# TestResitorArraySmd.net
KiCad netlist of a schematic drawn in EAGLE
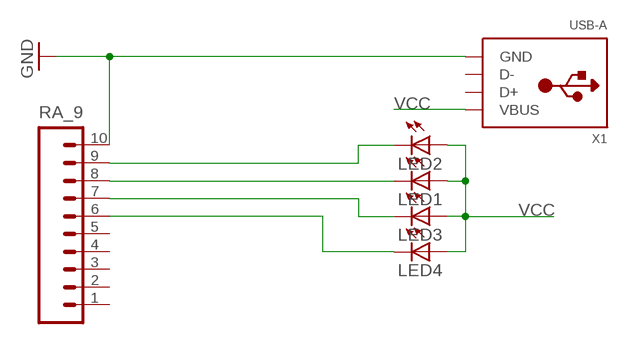
[diagram p0: schematic, sheet 1]

(export (version "E")
  (design (tool "Eeschema 10.0.6"))
  (components
    (comp (ref "LED1")
      (value "LEDSMT1206")
      (footprint "eagle-import:1206")
      (libsource (lib "eagle-import") (part "LEDSMT1206"))
    )
    (comp (ref "LED2")
      (value "LEDSMT1206")
      (footprint "eagle-import:1206")
      (libsource (lib "eagle-import") (part "LEDSMT1206"))
    )
    (comp (ref "LED3")
      (value "LEDSMT1206")
      (footprint "eagle-import:1206")
      (libsource (lib "eagle-import") (part "LEDSMT1206"))
    )
    (comp (ref "LED4")
      (value "LEDSMT1206")
      (footprint "eagle-import:1206")
      (libsource (lib "eagle-import") (part "LEDSMT1206"))
    )
    (comp (ref "RA_9")
      (value "M10SMD_MALE")
      (footprint "eagle-import:1X10_SMD_MALE")
      (libsource (lib "eagle-import") (part "M10SMD_MALE"))
    )
    (comp (ref "X1")
      (value "USB-A")
      (footprint "eagle-import:MOLEX_480371000")
      (libsource (lib "eagle-import") (part "USB-A"))
    )
  )
  (nets
    (net (code "1") (name "/VCC") (class "Default")
      (node (ref "LED1") (pin "A") (pinfunction "A_A") (pintype "passive"))
      (node (ref "LED2") (pin "A") (pinfunction "A_A") (pintype "passive"))
      (node (ref "LED3") (pin "A") (pinfunction "A_A") (pintype "passive"))
      (node (ref "LED4") (pin "A") (pinfunction "A_A") (pintype "passive"))
      (node (ref "X1") (pin "1") (pinfunction "VBUS_1") (pintype "power_in"))
    )
    (net (code "2") (name "GND") (class "Default")
      (node (ref "RA_9") (pin "10") (pinfunction "10_10") (pintype "passive"))
      (node (ref "X1") (pin "4") (pinfunction "GND_4") (pintype "power_in"))
    )
    (net (code "3") (name "Net-(LED1-PadC)") (class "Default")
      (node (ref "LED1") (pin "C") (pinfunction "C_C") (pintype "passive"))
      (node (ref "RA_9") (pin "8") (pinfunction "8_8") (pintype "passive"))
    )
    (net (code "4") (name "Net-(LED2-PadC)") (class "Default")
      (node (ref "LED2") (pin "C") (pinfunction "C_C") (pintype "passive"))
      (node (ref "RA_9") (pin "9") (pinfunction "9_9") (pintype "passive"))
    )
    (net (code "5") (name "Net-(LED3-PadC)") (class "Default")
      (node (ref "LED3") (pin "C") (pinfunction "C_C") (pintype "passive"))
      (node (ref "RA_9") (pin "7") (pinfunction "7_7") (pintype "passive"))
    )
    (net (code "6") (name "Net-(LED4-PadC)") (class "Default")
      (node (ref "LED4") (pin "C") (pinfunction "C_C") (pintype "passive"))
      (node (ref "RA_9") (pin "6") (pinfunction "6_6") (pintype "passive"))
    )
    (net (code "7") (name "unconnected-(RA_9-Pad1)") (class "Default")
      (node (ref "RA_9") (pin "1") (pinfunction "1_1") (pintype "passive"))
    )
    (net (code "8") (name "unconnected-(RA_9-Pad2)") (class "Default")
      (node (ref "RA_9") (pin "2") (pinfunction "2_2") (pintype "passive"))
    )
    (net (code "9") (name "unconnected-(RA_9-Pad3)") (class "Default")
      (node (ref "RA_9") (pin "3") (pinfunction "3_3") (pintype "passive"))
    )
    (net (code "10") (name "unconnected-(RA_9-Pad4)") (class "Default")
      (node (ref "RA_9") (pin "4") (pinfunction "4_4") (pintype "passive"))
    )
    (net (code "11") (name "unconnected-(RA_9-Pad5)") (class "Default")
      (node (ref "RA_9") (pin "5") (pinfunction "5_5") (pintype "passive"))
    )
    (net (code "12") (name "unconnected-(X1-D+-Pad3)") (class "Default")
      (node (ref "X1") (pin "3") (pinfunction "D+_3") (pintype "bidirectional"))
    )
    (net (code "13") (name "unconnected-(X1-D--Pad2)") (class "Default")
      (node (ref "X1") (pin "2") (pinfunction "D-_2") (pintype "bidirectional"))
    )
  )
)
